# board.net
KiCad netlist of a schematic drawn in EAGLE
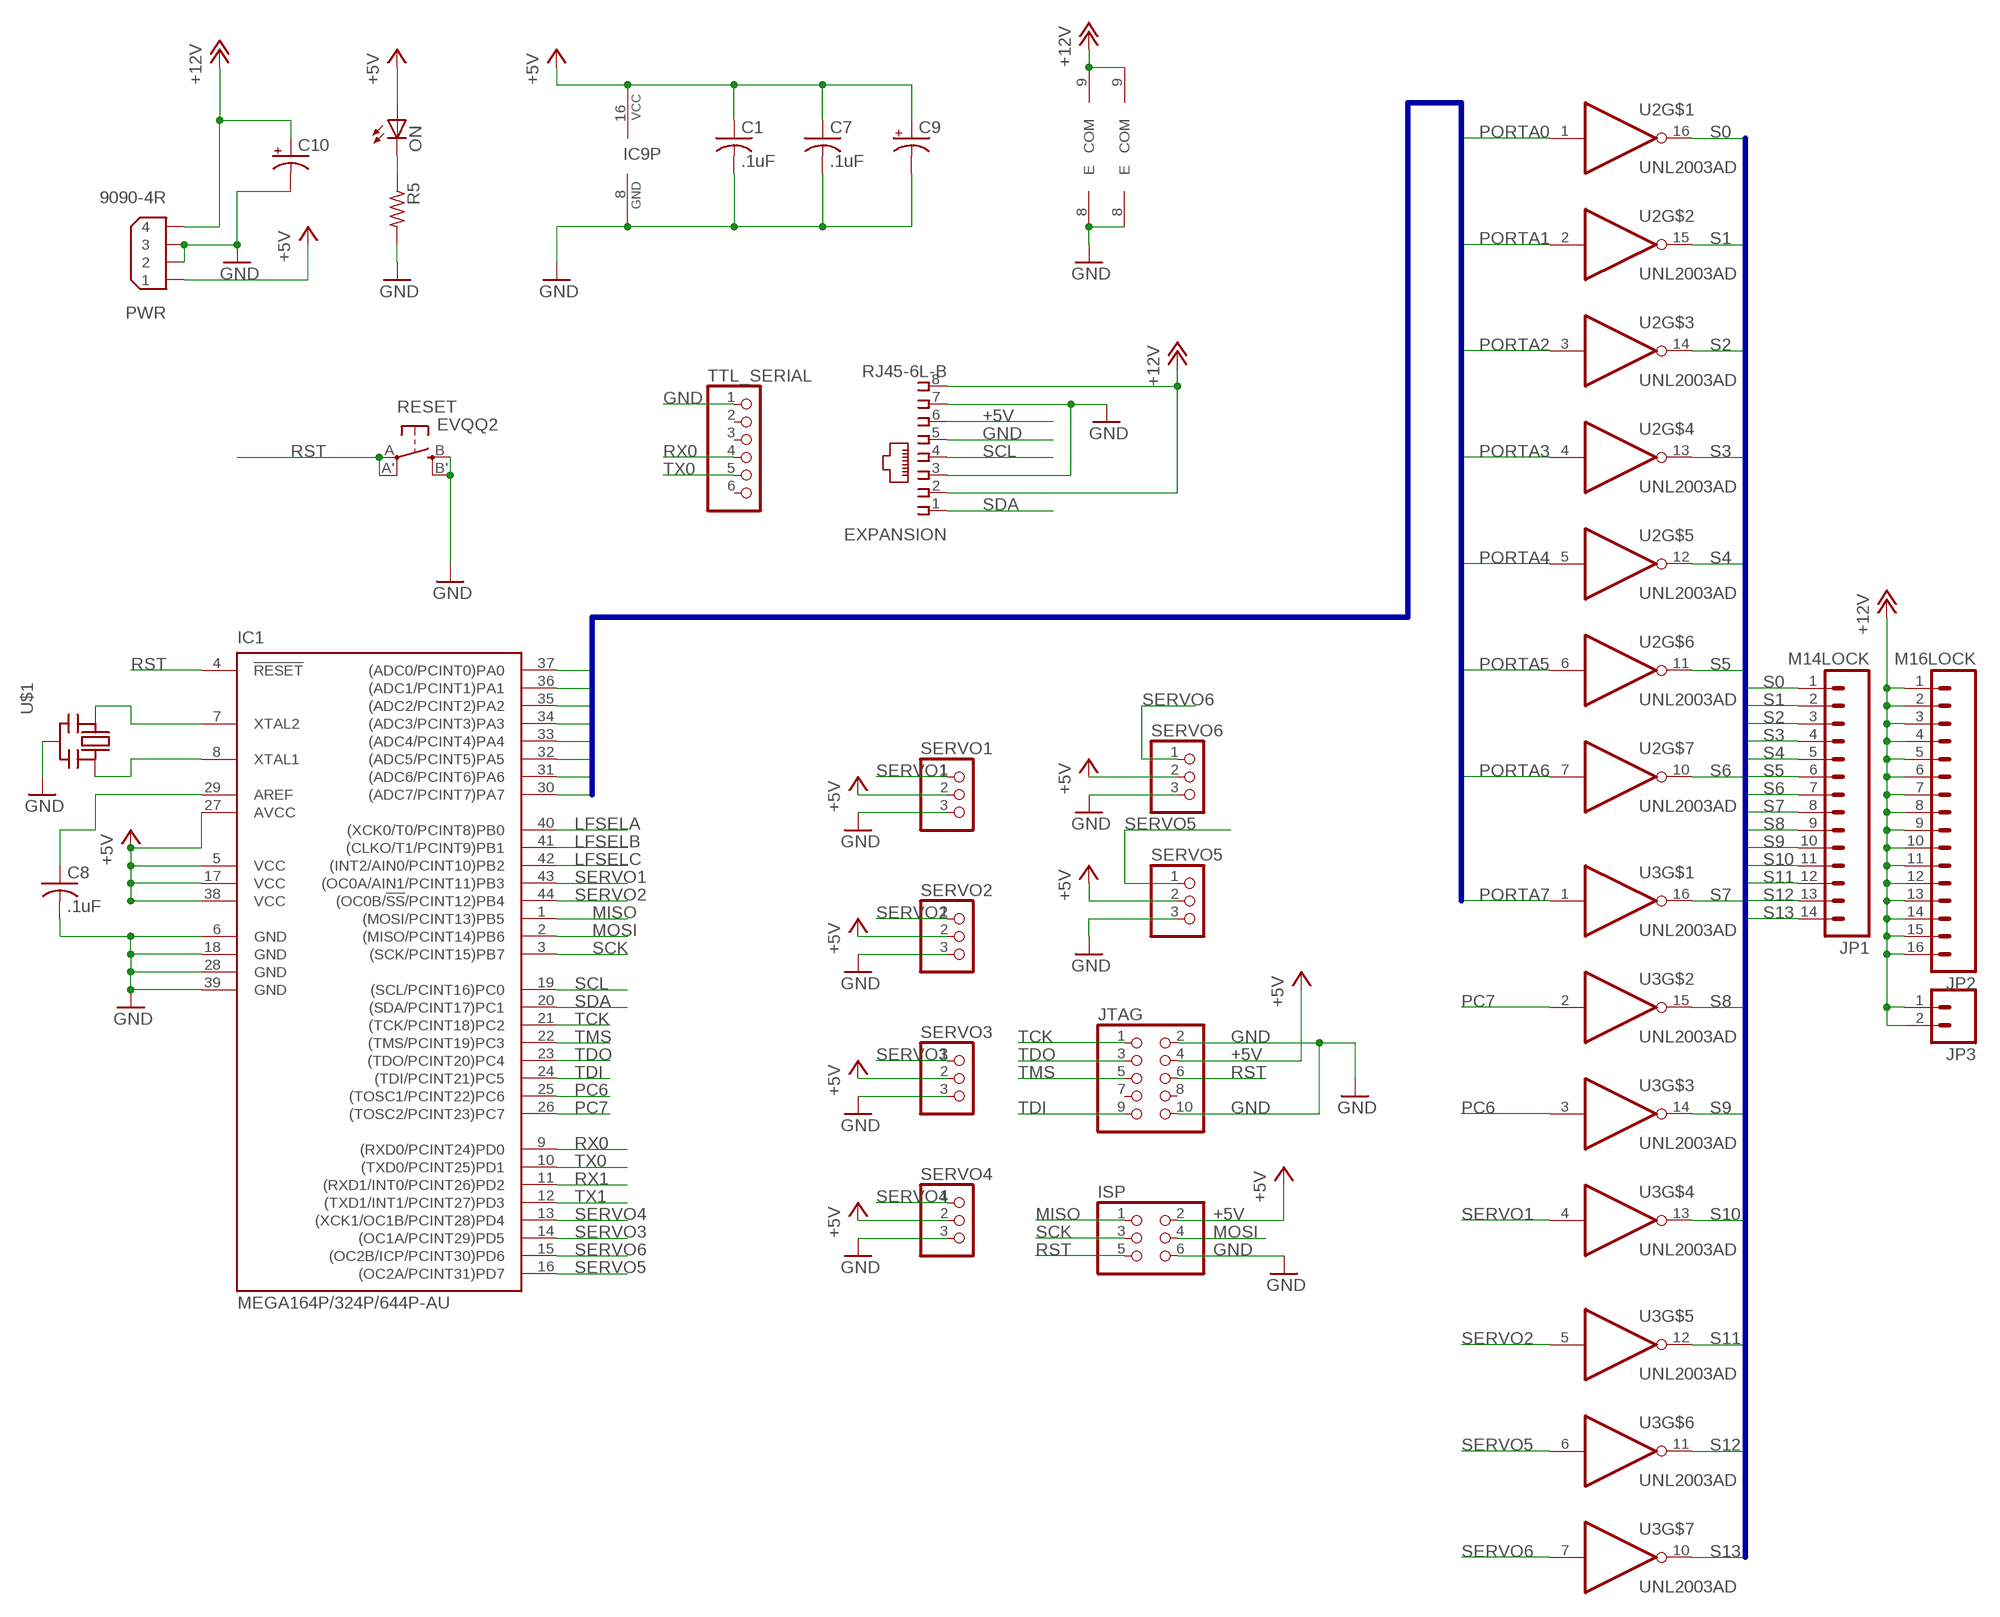
[diagram p0: schematic, sheet 1, part 1 of 2]
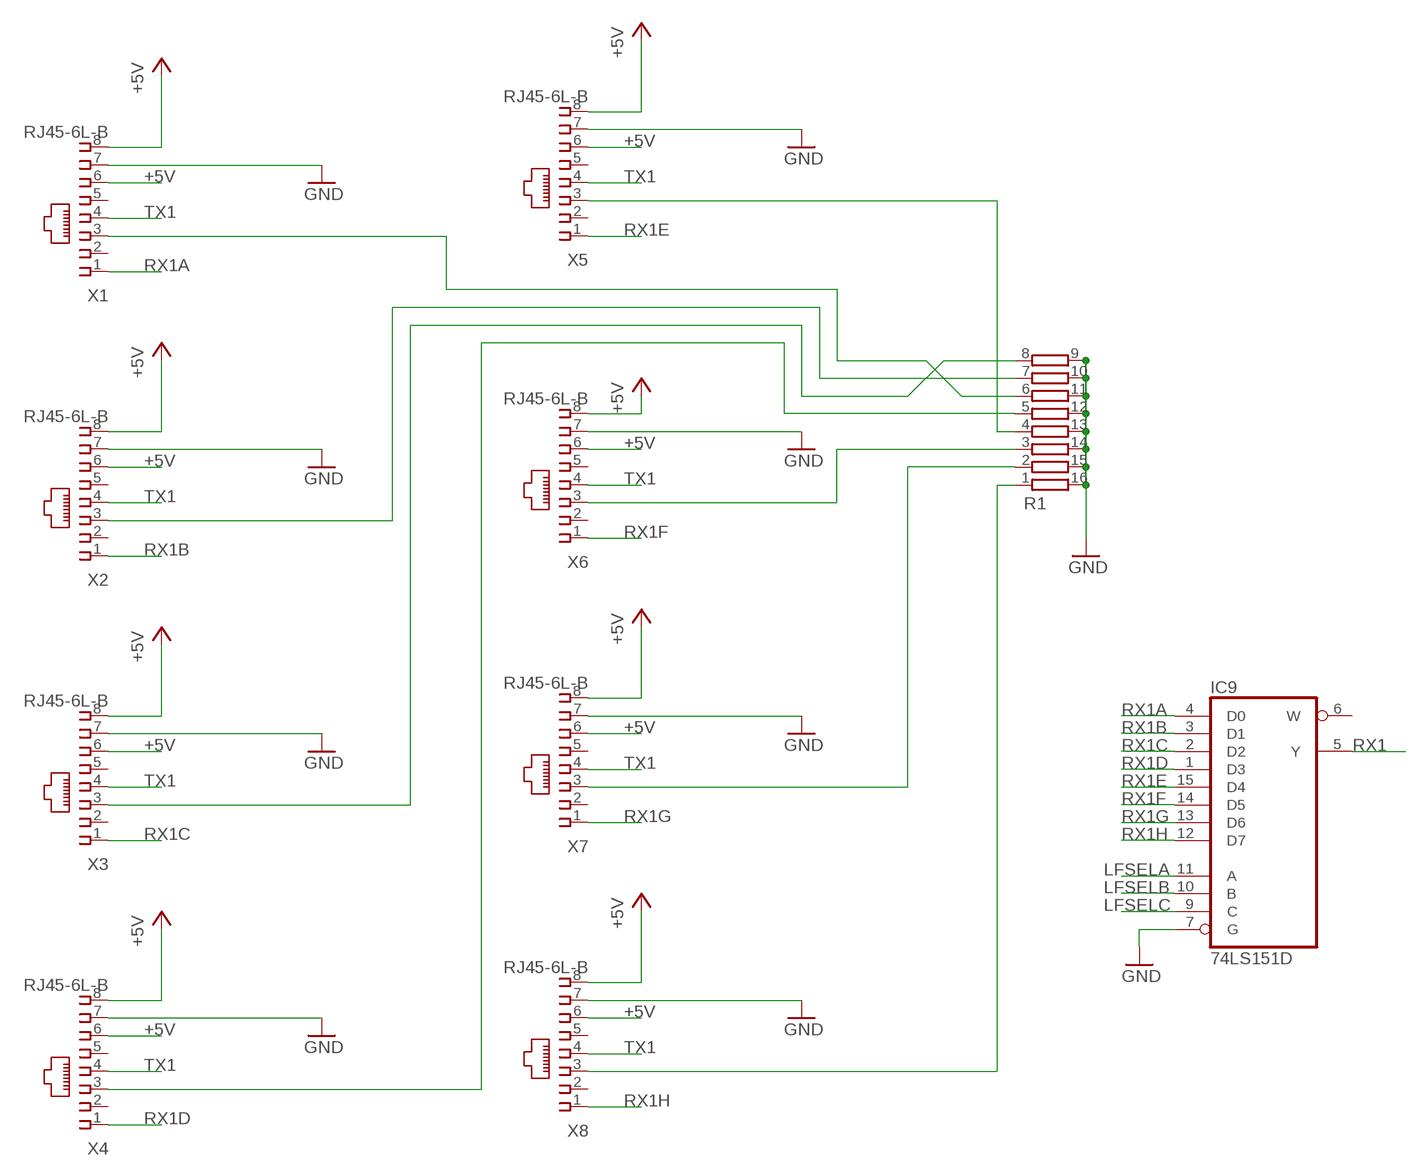
[diagram p1: schematic, sheet 1, part 2 of 2]

(export (version "E")
  (design (tool "Eeschema 10.0.6"))
  (components
    (comp (ref "C1")
      (value ".1uF")
      (footprint "eagle-import:C0805")
      (libsource (lib "eagle-import") (part "C-USC0805"))
    )
    (comp (ref "C7")
      (value ".1uF")
      (footprint "eagle-import:C0805")
      (libsource (lib "eagle-import") (part "C-USC0805"))
    )
    (comp (ref "C8")
      (value ".1uF")
      (footprint "eagle-import:C0805")
      (libsource (lib "eagle-import") (part "C-USC0805"))
    )
    (comp (ref "C9")
      (value "CPOL-USE2.5-7")
      (footprint "eagle-import:E2,5-7")
      (libsource (lib "eagle-import") (part "CPOL-USE2.5-7"))
    )
    (comp (ref "C10")
      (value "CPOL-USE2.5-7")
      (footprint "eagle-import:E2,5-7")
      (libsource (lib "eagle-import") (part "CPOL-USE2.5-7"))
    )
    (comp (ref "EXPANSION")
      (value "RJ45-6L-B")
      (footprint "eagle-import:RJ45-NO-SHIELD")
      (libsource (lib "eagle-import") (part "RJ45-6L-B"))
    )
    (comp (ref "IC1")
      (value "MEGA164P/324P/644P-AU")
      (footprint "eagle-import:TQFP44")
      (libsource (lib "eagle-import") (part "MEGA164P/324P/644P-AU"))
    )
    (comp (ref "IC9")
      (value "74LS151D")
      (footprint "eagle-import:SO16")
      (libsource (lib "eagle-import") (part "74151DLS"))
    )
    (comp (ref "ISP")
      (value "PINHD-2X3")
      (footprint "eagle-import:2X03")
      (libsource (lib "eagle-import") (part "PINHD-2X3"))
    )
    (comp (ref "JP1")
      (value "M14LOCK")
      (footprint "eagle-import:1X14_LOCK")
      (libsource (lib "eagle-import") (part "M14LOCK"))
    )
    (comp (ref "JP2")
      (value "M16LOCK")
      (footprint "eagle-import:1X16_LOCK")
      (libsource (lib "eagle-import") (part "M16LOCK"))
    )
    (comp (ref "JP3")
      (value "M02PTH")
      (footprint "eagle-import:1X02")
      (libsource (lib "eagle-import") (part "M02PTH"))
    )
    (comp (ref "JTAG")
      (value "PINHD-2X5")
      (footprint "eagle-import:2X05")
      (libsource (lib "eagle-import") (part "PINHD-2X5"))
    )
    (comp (ref "ON")
      (value "LEDCHIPLED_0805")
      (footprint "eagle-import:CHIPLED_0805")
      (libsource (lib "eagle-import") (part "LEDCHIPLED_0805"))
    )
    (comp (ref "PWR")
      (value "9090-4R")
      (footprint "eagle-import:9090-4R")
      (libsource (lib "eagle-import") (part "9090-4R"))
    )
    (comp (ref "R1")
      (value "2NBS16-8")
      (footprint "eagle-import:SO16")
      (libsource (lib "eagle-import") (part "2NBS16-8"))
    )
    (comp (ref "R5")
      (value "R-US_R0805")
      (footprint "eagle-import:R0805")
      (libsource (lib "eagle-import") (part "R-US_R0805"))
    )
    (comp (ref "RESET")
      (value "EVQQ2")
      (footprint "eagle-import:EVQ-Q2")
      (libsource (lib "eagle-import") (part "EVQQ2"))
    )
    (comp (ref "SERVO1")
      (value "PINHD-1X3")
      (footprint "eagle-import:1X03")
      (libsource (lib "eagle-import") (part "PINHD-1X3"))
    )
    (comp (ref "SERVO2")
      (value "PINHD-1X3")
      (footprint "eagle-import:1X03")
      (libsource (lib "eagle-import") (part "PINHD-1X3"))
    )
    (comp (ref "SERVO3")
      (value "PINHD-1X3")
      (footprint "eagle-import:1X03")
      (libsource (lib "eagle-import") (part "PINHD-1X3"))
    )
    (comp (ref "SERVO4")
      (value "PINHD-1X3")
      (footprint "eagle-import:1X03")
      (libsource (lib "eagle-import") (part "PINHD-1X3"))
    )
    (comp (ref "SERVO5")
      (value "PINHD-1X3")
      (footprint "eagle-import:1X03")
      (libsource (lib "eagle-import") (part "PINHD-1X3"))
    )
    (comp (ref "SERVO6")
      (value "PINHD-1X3")
      (footprint "eagle-import:1X03")
      (libsource (lib "eagle-import") (part "PINHD-1X3"))
    )
    (comp (ref "TTL_SERIAL")
      (value "PINHD-1X6")
      (footprint "eagle-import:1X06")
      (libsource (lib "eagle-import") (part "PINHD-1X6"))
    )
    (comp (ref "U$1")
      (value "CERMOSCILL-CSTCRG")
      (footprint "eagle-import:CSTCR-G")
      (libsource (lib "eagle-import") (part "CERMOSCILL-CSTCRG"))
    )
    (comp (ref "U2")
      (value "UNL2003AD")
      (footprint "eagle-import:SO16")
      (libsource (lib "eagle-import") (part "UNL2003AD"))
    )
    (comp (ref "U3")
      (value "UNL2003AD")
      (footprint "eagle-import:SO16")
      (libsource (lib "eagle-import") (part "UNL2003AD"))
    )
    (comp (ref "X1")
      (value "RJ45-6L-B")
      (footprint "eagle-import:RJ45-NO-SHIELD")
      (libsource (lib "eagle-import") (part "RJ45-6L-B"))
    )
    (comp (ref "X2")
      (value "RJ45-6L-B")
      (footprint "eagle-import:RJ45-NO-SHIELD")
      (libsource (lib "eagle-import") (part "RJ45-6L-B"))
    )
    (comp (ref "X3")
      (value "RJ45-6L-B")
      (footprint "eagle-import:RJ45-NO-SHIELD")
      (libsource (lib "eagle-import") (part "RJ45-6L-B"))
    )
    (comp (ref "X4")
      (value "RJ45-6L-B")
      (footprint "eagle-import:RJ45-NO-SHIELD")
      (libsource (lib "eagle-import") (part "RJ45-6L-B"))
    )
    (comp (ref "X5")
      (value "RJ45-6L-B")
      (footprint "eagle-import:RJ45-NO-SHIELD")
      (libsource (lib "eagle-import") (part "RJ45-6L-B"))
    )
    (comp (ref "X6")
      (value "RJ45-6L-B")
      (footprint "eagle-import:RJ45-NO-SHIELD")
      (libsource (lib "eagle-import") (part "RJ45-6L-B"))
    )
    (comp (ref "X7")
      (value "RJ45-6L-B")
      (footprint "eagle-import:RJ45-NO-SHIELD")
      (libsource (lib "eagle-import") (part "RJ45-6L-B"))
    )
    (comp (ref "X8")
      (value "RJ45-6L-B")
      (footprint "eagle-import:RJ45-NO-SHIELD")
      (libsource (lib "eagle-import") (part "RJ45-6L-B"))
    )
  )
  (nets
    (net (code "1") (name "+5V") (class "Default")
      (node (ref "C1") (pin "1") (pinfunction "1_1") (pintype "passive"))
      (node (ref "C7") (pin "1") (pinfunction "1_1") (pintype "passive"))
      (node (ref "C9") (pin "+") (pinfunction "+_+") (pintype "passive"))
      (node (ref "EXPANSION") (pin "6") (pinfunction "6_6") (pintype "passive"))
      (node (ref "IC1") (pin "17") (pinfunction "VCC_17") (pintype "power_in"))
      (node (ref "IC1") (pin "27") (pinfunction "AVCC_27") (pintype "power_in"))
      (node (ref "IC1") (pin "38") (pinfunction "VCC_38") (pintype "power_in"))
      (node (ref "IC1") (pin "5") (pinfunction "VCC_5") (pintype "power_in"))
      (node (ref "IC9") (pin "16") (pinfunction "VCC_16") (pintype "power_in"))
      (node (ref "ISP") (pin "2") (pinfunction "2_2") (pintype "passive"))
      (node (ref "JTAG") (pin "4") (pinfunction "4_4") (pintype "passive"))
      (node (ref "ON") (pin "A") (pinfunction "A_A") (pintype "passive"))
      (node (ref "PWR") (pin "1") (pinfunction "1_1") (pintype "passive"))
      (node (ref "SERVO1") (pin "2") (pinfunction "2_2") (pintype "passive"))
      (node (ref "SERVO2") (pin "2") (pinfunction "2_2") (pintype "passive"))
      (node (ref "SERVO3") (pin "2") (pinfunction "2_2") (pintype "passive"))
      (node (ref "SERVO4") (pin "2") (pinfunction "2_2") (pintype "passive"))
      (node (ref "SERVO5") (pin "2") (pinfunction "2_2") (pintype "passive"))
      (node (ref "SERVO6") (pin "2") (pinfunction "2_2") (pintype "passive"))
      (node (ref "X1") (pin "6") (pinfunction "6_6") (pintype "passive"))
      (node (ref "X1") (pin "8") (pinfunction "8_8") (pintype "passive"))
      (node (ref "X2") (pin "6") (pinfunction "6_6") (pintype "passive"))
      (node (ref "X2") (pin "8") (pinfunction "8_8") (pintype "passive"))
      (node (ref "X3") (pin "6") (pinfunction "6_6") (pintype "passive"))
      (node (ref "X3") (pin "8") (pinfunction "8_8") (pintype "passive"))
      (node (ref "X4") (pin "6") (pinfunction "6_6") (pintype "passive"))
      (node (ref "X4") (pin "8") (pinfunction "8_8") (pintype "passive"))
      (node (ref "X5") (pin "6") (pinfunction "6_6") (pintype "passive"))
      (node (ref "X5") (pin "8") (pinfunction "8_8") (pintype "passive"))
      (node (ref "X6") (pin "6") (pinfunction "6_6") (pintype "passive"))
      (node (ref "X6") (pin "8") (pinfunction "8_8") (pintype "passive"))
      (node (ref "X7") (pin "6") (pinfunction "6_6") (pintype "passive"))
      (node (ref "X7") (pin "8") (pinfunction "8_8") (pintype "passive"))
      (node (ref "X8") (pin "6") (pinfunction "6_6") (pintype "passive"))
      (node (ref "X8") (pin "8") (pinfunction "8_8") (pintype "passive"))
    )
    (net (code "2") (name "+12V") (class "Default")
      (node (ref "C10") (pin "+") (pinfunction "+_+") (pintype "passive"))
      (node (ref "EXPANSION") (pin "2") (pinfunction "2_2") (pintype "passive"))
      (node (ref "EXPANSION") (pin "8") (pinfunction "8_8") (pintype "passive"))
      (node (ref "JP2") (pin "1") (pinfunction "1_1") (pintype "passive"))
      (node (ref "JP2") (pin "10") (pinfunction "10_10") (pintype "passive"))
      (node (ref "JP2") (pin "11") (pinfunction "11_11") (pintype "passive"))
      (node (ref "JP2") (pin "12") (pinfunction "12_12") (pintype "passive"))
      (node (ref "JP2") (pin "13") (pinfunction "13_13") (pintype "passive"))
      (node (ref "JP2") (pin "14") (pinfunction "14_14") (pintype "passive"))
      (node (ref "JP2") (pin "15") (pinfunction "15_15") (pintype "passive"))
      (node (ref "JP2") (pin "16") (pinfunction "16_16") (pintype "passive"))
      (node (ref "JP2") (pin "2") (pinfunction "2_2") (pintype "passive"))
      (node (ref "JP2") (pin "3") (pinfunction "3_3") (pintype "passive"))
      (node (ref "JP2") (pin "4") (pinfunction "4_4") (pintype "passive"))
      (node (ref "JP2") (pin "5") (pinfunction "5_5") (pintype "passive"))
      (node (ref "JP2") (pin "6") (pinfunction "6_6") (pintype "passive"))
      (node (ref "JP2") (pin "7") (pinfunction "7_7") (pintype "passive"))
      (node (ref "JP2") (pin "8") (pinfunction "8_8") (pintype "passive"))
      (node (ref "JP2") (pin "9") (pinfunction "9_9") (pintype "passive"))
      (node (ref "JP3") (pin "1") (pinfunction "1_1") (pintype "passive"))
      (node (ref "JP3") (pin "2") (pinfunction "2_2") (pintype "passive"))
      (node (ref "PWR") (pin "4") (pinfunction "4_4") (pintype "passive"))
      (node (ref "U2") (pin "9") (pinfunction "COM_9") (pintype "power_in"))
      (node (ref "U3") (pin "9") (pinfunction "COM_9") (pintype "power_in"))
    )
    (net (code "3") (name "/LFSELA") (class "Default")
      (node (ref "IC1") (pin "40") (pinfunction "(XCK0/T0/PCINT8)PB0_40") (pintype "bidirectional"))
      (node (ref "IC9") (pin "11") (pinfunction "A_11") (pintype "input"))
    )
    (net (code "4") (name "/LFSELB") (class "Default")
      (node (ref "IC1") (pin "41") (pinfunction "(CLKO/T1/PCINT9)PB1_41") (pintype "bidirectional"))
      (node (ref "IC9") (pin "10") (pinfunction "B_10") (pintype "input"))
    )
    (net (code "5") (name "/LFSELC") (class "Default")
      (node (ref "IC1") (pin "42") (pinfunction "(INT2/AIN0/PCINT10)PB2_42") (pintype "bidirectional"))
      (node (ref "IC9") (pin "9") (pinfunction "C_9") (pintype "input"))
    )
    (net (code "6") (name "/MISO") (class "Default")
      (node (ref "IC1") (pin "1") (pinfunction "(MOSI/PCINT13)PB5_1") (pintype "bidirectional"))
      (node (ref "ISP") (pin "1") (pinfunction "1_1") (pintype "passive"))
    )
    (net (code "7") (name "/MOSI") (class "Default")
      (node (ref "IC1") (pin "2") (pinfunction "(MISO/PCINT14)PB6_2") (pintype "bidirectional"))
      (node (ref "ISP") (pin "4") (pinfunction "4_4") (pintype "passive"))
    )
    (net (code "8") (name "/PC6") (class "Default")
      (node (ref "IC1") (pin "25") (pinfunction "(TOSC1/PCINT22)PC6_25") (pintype "bidirectional"))
      (node (ref "U3") (pin "3") (pinfunction "I_3") (pintype "input"))
    )
    (net (code "9") (name "/PC7") (class "Default")
      (node (ref "IC1") (pin "26") (pinfunction "(TOSC2/PCINT23)PC7_26") (pintype "bidirectional"))
      (node (ref "U3") (pin "2") (pinfunction "I_2") (pintype "input"))
    )
    (net (code "10") (name "/PORTA0") (class "Default")
      (node (ref "IC1") (pin "37") (pinfunction "(ADC0/PCINT0)PA0_37") (pintype "bidirectional"))
      (node (ref "U2") (pin "1") (pinfunction "I_1") (pintype "input"))
    )
    (net (code "11") (name "/PORTA1") (class "Default")
      (node (ref "IC1") (pin "36") (pinfunction "(ADC1/PCINT1)PA1_36") (pintype "bidirectional"))
      (node (ref "U2") (pin "2") (pinfunction "I_2") (pintype "input"))
    )
    (net (code "12") (name "/PORTA2") (class "Default")
      (node (ref "IC1") (pin "35") (pinfunction "(ADC2/PCINT2)PA2_35") (pintype "bidirectional"))
      (node (ref "U2") (pin "3") (pinfunction "I_3") (pintype "input"))
    )
    (net (code "13") (name "/PORTA3") (class "Default")
      (node (ref "IC1") (pin "34") (pinfunction "(ADC3/PCINT3)PA3_34") (pintype "bidirectional"))
      (node (ref "U2") (pin "4") (pinfunction "I_4") (pintype "input"))
    )
    (net (code "14") (name "/PORTA4") (class "Default")
      (node (ref "IC1") (pin "33") (pinfunction "(ADC4/PCINT4)PA4_33") (pintype "bidirectional"))
      (node (ref "U2") (pin "5") (pinfunction "I_5") (pintype "input"))
    )
    (net (code "15") (name "/PORTA5") (class "Default")
      (node (ref "IC1") (pin "32") (pinfunction "(ADC5/PCINT5)PA5_32") (pintype "bidirectional"))
      (node (ref "U2") (pin "6") (pinfunction "I_6") (pintype "input"))
    )
    (net (code "16") (name "/PORTA6") (class "Default")
      (node (ref "IC1") (pin "31") (pinfunction "(ADC6/PCINT6)PA6_31") (pintype "bidirectional"))
      (node (ref "U2") (pin "7") (pinfunction "I_7") (pintype "input"))
    )
    (net (code "17") (name "/PORTA7") (class "Default")
      (node (ref "IC1") (pin "30") (pinfunction "(ADC7/PCINT7)PA7_30") (pintype "bidirectional"))
      (node (ref "U3") (pin "1") (pinfunction "I_1") (pintype "input"))
    )
    (net (code "18") (name "/RST") (class "Default")
      (node (ref "IC1") (pin "4") (pinfunction "~{RESET}_4") (pintype "input"))
      (node (ref "ISP") (pin "5") (pinfunction "5_5") (pintype "passive"))
      (node (ref "JTAG") (pin "6") (pinfunction "6_6") (pintype "passive"))
      (node (ref "RESET") (pin "A") (pinfunction "P_A") (pintype "passive"))
      (node (ref "RESET") (pin "A'") (pinfunction "P1_A'") (pintype "passive"))
    )
    (net (code "19") (name "/RX0") (class "Default")
      (node (ref "IC1") (pin "9") (pinfunction "(RXD0/PCINT24)PD0_9") (pintype "bidirectional"))
      (node (ref "TTL_SERIAL") (pin "4") (pinfunction "4_4") (pintype "passive"))
    )
    (net (code "20") (name "/RX1") (class "Default")
      (node (ref "IC1") (pin "11") (pinfunction "(RXD1/INT0/PCINT26)PD2_11") (pintype "bidirectional"))
      (node (ref "IC9") (pin "5") (pinfunction "Y_5") (pintype "output"))
    )
    (net (code "21") (name "/RX1A") (class "Default")
      (node (ref "IC9") (pin "4") (pinfunction "D0_4") (pintype "input"))
      (node (ref "X1") (pin "1") (pinfunction "1_1") (pintype "passive"))
    )
    (net (code "22") (name "/RX1B") (class "Default")
      (node (ref "IC9") (pin "3") (pinfunction "D1_3") (pintype "input"))
      (node (ref "X2") (pin "1") (pinfunction "1_1") (pintype "passive"))
    )
    (net (code "23") (name "/RX1C") (class "Default")
      (node (ref "IC9") (pin "2") (pinfunction "D2_2") (pintype "input"))
      (node (ref "X3") (pin "1") (pinfunction "1_1") (pintype "passive"))
    )
    (net (code "24") (name "/RX1D") (class "Default")
      (node (ref "IC9") (pin "1") (pinfunction "D3_1") (pintype "input"))
      (node (ref "X4") (pin "1") (pinfunction "1_1") (pintype "passive"))
    )
    (net (code "25") (name "/RX1E") (class "Default")
      (node (ref "IC9") (pin "15") (pinfunction "D4_15") (pintype "input"))
      (node (ref "X5") (pin "1") (pinfunction "1_1") (pintype "passive"))
    )
    (net (code "26") (name "/RX1F") (class "Default")
      (node (ref "IC9") (pin "14") (pinfunction "D5_14") (pintype "input"))
      (node (ref "X6") (pin "1") (pinfunction "1_1") (pintype "passive"))
    )
    (net (code "27") (name "/RX1G") (class "Default")
      (node (ref "IC9") (pin "13") (pinfunction "D6_13") (pintype "input"))
      (node (ref "X7") (pin "1") (pinfunction "1_1") (pintype "passive"))
    )
    (net (code "28") (name "/RX1H") (class "Default")
      (node (ref "IC9") (pin "12") (pinfunction "D7_12") (pintype "input"))
      (node (ref "X8") (pin "1") (pinfunction "1_1") (pintype "passive"))
    )
    (net (code "29") (name "/S0") (class "Default")
      (node (ref "JP1") (pin "1") (pinfunction "1_1") (pintype "passive"))
      (node (ref "U2") (pin "16") (pinfunction "O_16") (pintype "output"))
    )
    (net (code "30") (name "/S1") (class "Default")
      (node (ref "JP1") (pin "2") (pinfunction "2_2") (pintype "passive"))
      (node (ref "U2") (pin "15") (pinfunction "O_15") (pintype "output"))
    )
    (net (code "31") (name "/S2") (class "Default")
      (node (ref "JP1") (pin "3") (pinfunction "3_3") (pintype "passive"))
      (node (ref "U2") (pin "14") (pinfunction "O_14") (pintype "output"))
    )
    (net (code "32") (name "/S3") (class "Default")
      (node (ref "JP1") (pin "4") (pinfunction "4_4") (pintype "passive"))
      (node (ref "U2") (pin "13") (pinfunction "O_13") (pintype "output"))
    )
    (net (code "33") (name "/S4") (class "Default")
      (node (ref "JP1") (pin "5") (pinfunction "5_5") (pintype "passive"))
      (node (ref "U2") (pin "12") (pinfunction "O_12") (pintype "output"))
    )
    (net (code "34") (name "/S5") (class "Default")
      (node (ref "JP1") (pin "6") (pinfunction "6_6") (pintype "passive"))
      (node (ref "U2") (pin "11") (pinfunction "O_11") (pintype "output"))
    )
    (net (code "35") (name "/S6") (class "Default")
      (node (ref "JP1") (pin "7") (pinfunction "7_7") (pintype "passive"))
      (node (ref "U2") (pin "10") (pinfunction "O_10") (pintype "output"))
    )
    (net (code "36") (name "/S7") (class "Default")
      (node (ref "JP1") (pin "8") (pinfunction "8_8") (pintype "passive"))
      (node (ref "U3") (pin "16") (pinfunction "O_16") (pintype "output"))
    )
    (net (code "37") (name "/S8") (class "Default")
      (node (ref "JP1") (pin "9") (pinfunction "9_9") (pintype "passive"))
      (node (ref "U3") (pin "15") (pinfunction "O_15") (pintype "output"))
    )
    (net (code "38") (name "/S9") (class "Default")
      (node (ref "JP1") (pin "10") (pinfunction "10_10") (pintype "passive"))
      (node (ref "U3") (pin "14") (pinfunction "O_14") (pintype "output"))
    )
    (net (code "39") (name "/S10") (class "Default")
      (node (ref "JP1") (pin "11") (pinfunction "11_11") (pintype "passive"))
      (node (ref "U3") (pin "13") (pinfunction "O_13") (pintype "output"))
    )
    (net (code "40") (name "/S11") (class "Default")
      (node (ref "JP1") (pin "12") (pinfunction "12_12") (pintype "passive"))
      (node (ref "U3") (pin "12") (pinfunction "O_12") (pintype "output"))
    )
    (net (code "41") (name "/S12") (class "Default")
      (node (ref "JP1") (pin "13") (pinfunction "13_13") (pintype "passive"))
      (node (ref "U3") (pin "11") (pinfunction "O_11") (pintype "output"))
    )
    (net (code "42") (name "/S13") (class "Default")
      (node (ref "JP1") (pin "14") (pinfunction "14_14") (pintype "passive"))
      (node (ref "U3") (pin "10") (pinfunction "O_10") (pintype "output"))
    )
    (net (code "43") (name "/SCK") (class "Default")
      (node (ref "IC1") (pin "3") (pinfunction "(SCK/PCINT15)PB7_3") (pintype "bidirectional"))
      (node (ref "ISP") (pin "3") (pinfunction "3_3") (pintype "passive"))
    )
    (net (code "44") (name "/SCL") (class "Default")
      (node (ref "EXPANSION") (pin "4") (pinfunction "4_4") (pintype "passive"))
      (node (ref "IC1") (pin "19") (pinfunction "(SCL/PCINT16)PC0_19") (pintype "bidirectional"))
    )
    (net (code "45") (name "/SDA") (class "Default")
      (node (ref "EXPANSION") (pin "1") (pinfunction "1_1") (pintype "passive"))
      (node (ref "IC1") (pin "20") (pinfunction "(SDA/PCINT17)PC1_20") (pintype "bidirectional"))
    )
    (net (code "46") (name "/SERVO1") (class "Default")
      (node (ref "IC1") (pin "43") (pinfunction "(OC0A/AIN1/PCINT11)PB3_43") (pintype "bidirectional"))
      (node (ref "SERVO1") (pin "1") (pinfunction "1_1") (pintype "passive"))
      (node (ref "U3") (pin "4") (pinfunction "I_4") (pintype "input"))
    )
    (net (code "47") (name "/SERVO2") (class "Default")
      (node (ref "IC1") (pin "44") (pinfunction "(OC0B/~{SS}/PCINT12)PB4_44") (pintype "bidirectional"))
      (node (ref "SERVO2") (pin "1") (pinfunction "1_1") (pintype "passive"))
      (node (ref "U3") (pin "5") (pinfunction "I_5") (pintype "input"))
    )
    (net (code "48") (name "/SERVO3") (class "Default")
      (node (ref "IC1") (pin "14") (pinfunction "(OC1A/PCINT29)PD5_14") (pintype "bidirectional"))
      (node (ref "SERVO3") (pin "1") (pinfunction "1_1") (pintype "passive"))
    )
    (net (code "49") (name "/SERVO4") (class "Default")
      (node (ref "IC1") (pin "13") (pinfunction "(XCK1/OC1B/PCINT28)PD4_13") (pintype "bidirectional"))
      (node (ref "SERVO4") (pin "1") (pinfunction "1_1") (pintype "passive"))
    )
    (net (code "50") (name "/SERVO5") (class "Default")
      (node (ref "IC1") (pin "16") (pinfunction "(OC2A/PCINT31)PD7_16") (pintype "bidirectional"))
      (node (ref "SERVO5") (pin "1") (pinfunction "1_1") (pintype "passive"))
      (node (ref "U3") (pin "6") (pinfunction "I_6") (pintype "input"))
    )
    (net (code "51") (name "/SERVO6") (class "Default")
      (node (ref "IC1") (pin "15") (pinfunction "(OC2B/ICP/PCINT30)PD6_15") (pintype "bidirectional"))
      (node (ref "SERVO6") (pin "1") (pinfunction "1_1") (pintype "passive"))
      (node (ref "U3") (pin "7") (pinfunction "I_7") (pintype "input"))
    )
    (net (code "52") (name "/TCK") (class "Default")
      (node (ref "IC1") (pin "21") (pinfunction "(TCK/PCINT18)PC2_21") (pintype "bidirectional"))
      (node (ref "JTAG") (pin "1") (pinfunction "1_1") (pintype "passive"))
    )
    (net (code "53") (name "/TDI") (class "Default")
      (node (ref "IC1") (pin "24") (pinfunction "(TDI/PCINT21)PC5_24") (pintype "bidirectional"))
      (node (ref "JTAG") (pin "9") (pinfunction "9_9") (pintype "passive"))
    )
    (net (code "54") (name "/TDO") (class "Default")
      (node (ref "IC1") (pin "23") (pinfunction "(TDO/PCINT20)PC4_23") (pintype "bidirectional"))
      (node (ref "JTAG") (pin "3") (pinfunction "3_3") (pintype "passive"))
    )
    (net (code "55") (name "/TMS") (class "Default")
      (node (ref "IC1") (pin "22") (pinfunction "(TMS/PCINT19)PC3_22") (pintype "bidirectional"))
      (node (ref "JTAG") (pin "5") (pinfunction "5_5") (pintype "passive"))
    )
    (net (code "56") (name "/TX0") (class "Default")
      (node (ref "IC1") (pin "10") (pinfunction "(TXD0/PCINT25)PD1_10") (pintype "bidirectional"))
      (node (ref "TTL_SERIAL") (pin "5") (pinfunction "5_5") (pintype "passive"))
    )
    (net (code "57") (name "/TX1") (class "Default")
      (node (ref "IC1") (pin "12") (pinfunction "(TXD1/INT1/PCINT27)PD3_12") (pintype "bidirectional"))
      (node (ref "X1") (pin "4") (pinfunction "4_4") (pintype "passive"))
      (node (ref "X2") (pin "4") (pinfunction "4_4") (pintype "passive"))
      (node (ref "X3") (pin "4") (pinfunction "4_4") (pintype "passive"))
      (node (ref "X4") (pin "4") (pinfunction "4_4") (pintype "passive"))
      (node (ref "X5") (pin "4") (pinfunction "4_4") (pintype "passive"))
      (node (ref "X6") (pin "4") (pinfunction "4_4") (pintype "passive"))
      (node (ref "X7") (pin "4") (pinfunction "4_4") (pintype "passive"))
      (node (ref "X8") (pin "4") (pinfunction "4_4") (pintype "passive"))
    )
    (net (code "58") (name "GND") (class "Default")
      (node (ref "C1") (pin "2") (pinfunction "2_2") (pintype "passive"))
      (node (ref "C10") (pin "-") (pinfunction "-_-") (pintype "passive"))
      (node (ref "C7") (pin "2") (pinfunction "2_2") (pintype "passive"))
      (node (ref "C8") (pin "2") (pinfunction "2_2") (pintype "passive"))
      (node (ref "C9") (pin "-") (pinfunction "-_-") (pintype "passive"))
      (node (ref "EXPANSION") (pin "3") (pinfunction "3_3") (pintype "passive"))
      (node (ref "EXPANSION") (pin "5") (pinfunction "5_5") (pintype "passive"))
      (node (ref "EXPANSION") (pin "7") (pinfunction "7_7") (pintype "passive"))
      (node (ref "IC1") (pin "18") (pinfunction "GND_18") (pintype "power_in"))
      (node (ref "IC1") (pin "28") (pinfunction "GND_28") (pintype "power_in"))
      (node (ref "IC1") (pin "39") (pinfunction "GND_39") (pintype "power_in"))
      (node (ref "IC1") (pin "6") (pinfunction "GND_6") (pintype "power_in"))
      (node (ref "IC9") (pin "7") (pinfunction "G_7") (pintype "input"))
      (node (ref "IC9") (pin "8") (pinfunction "GND_8") (pintype "power_in"))
      (node (ref "ISP") (pin "6") (pinfunction "6_6") (pintype "passive"))
      (node (ref "JTAG") (pin "10") (pinfunction "10_10") (pintype "passive"))
      (node (ref "JTAG") (pin "2") (pinfunction "2_2") (pintype "passive"))
      (node (ref "PWR") (pin "2") (pinfunction "2_2") (pintype "passive"))
      (node (ref "PWR") (pin "3") (pinfunction "3_3") (pintype "passive"))
      (node (ref "R1") (pin "10") (pinfunction "10_10") (pintype "passive"))
      (node (ref "R1") (pin "11") (pinfunction "11_11") (pintype "passive"))
      (node (ref "R1") (pin "12") (pinfunction "12_12") (pintype "passive"))
      (node (ref "R1") (pin "13") (pinfunction "13_13") (pintype "passive"))
      (node (ref "R1") (pin "14") (pinfunction "14_14") (pintype "passive"))
      (node (ref "R1") (pin "15") (pinfunction "15_15") (pintype "passive"))
      (node (ref "R1") (pin "16") (pinfunction "16_16") (pintype "passive"))
      (node (ref "R1") (pin "9") (pinfunction "9_9") (pintype "passive"))
      (node (ref "R5") (pin "2") (pinfunction "2_2") (pintype "passive"))
      (node (ref "RESET") (pin "B") (pinfunction "S_B") (pintype "passive"))
      (node (ref "RESET") (pin "B'") (pinfunction "S1_B'") (pintype "passive"))
      (node (ref "SERVO1") (pin "3") (pinfunction "3_3") (pintype "passive"))
      (node (ref "SERVO2") (pin "3") (pinfunction "3_3") (pintype "passive"))
      (node (ref "SERVO3") (pin "3") (pinfunction "3_3") (pintype "passive"))
      (node (ref "SERVO4") (pin "3") (pinfunction "3_3") (pintype "passive"))
      (node (ref "SERVO5") (pin "3") (pinfunction "3_3") (pintype "passive"))
      (node (ref "SERVO6") (pin "3") (pinfunction "3_3") (pintype "passive"))
      (node (ref "TTL_SERIAL") (pin "1") (pinfunction "1_1") (pintype "passive"))
      (node (ref "U$1") (pin "2") (pinfunction "GND_2") (pintype "bidirectional"))
      (node (ref "U2") (pin "8") (pinfunction "E_8") (pintype "power_in"))
      (node (ref "U3") (pin "8") (pinfunction "E_8") (pintype "power_in"))
      (node (ref "X1") (pin "7") (pinfunction "7_7") (pintype "passive"))
      (node (ref "X2") (pin "7") (pinfunction "7_7") (pintype "passive"))
      (node (ref "X3") (pin "7") (pinfunction "7_7") (pintype "passive"))
      (node (ref "X4") (pin "7") (pinfunction "7_7") (pintype "passive"))
      (node (ref "X5") (pin "7") (pinfunction "7_7") (pintype "passive"))
      (node (ref "X6") (pin "7") (pinfunction "7_7") (pintype "passive"))
      (node (ref "X7") (pin "7") (pinfunction "7_7") (pintype "passive"))
      (node (ref "X8") (pin "7") (pinfunction "7_7") (pintype "passive"))
    )
    (net (code "59") (name "Net-(IC1-AREF)") (class "Default")
      (node (ref "C8") (pin "1") (pinfunction "1_1") (pintype "passive"))
      (node (ref "IC1") (pin "29") (pinfunction "AREF_29") (pintype "power_in"))
    )
    (net (code "60") (name "Net-(IC1-XTAL1)") (class "Default")
      (node (ref "IC1") (pin "8") (pinfunction "XTAL1_8") (pintype "input"))
      (node (ref "U$1") (pin "3") (pinfunction "OUT_3") (pintype "bidirectional"))
    )
    (net (code "61") (name "Net-(IC1-XTAL2)") (class "Default")
      (node (ref "IC1") (pin "7") (pinfunction "XTAL2_7") (pintype "output"))
      (node (ref "U$1") (pin "1") (pinfunction "IN_1") (pintype "bidirectional"))
    )
    (net (code "62") (name "Net-(ON-PadC)") (class "Default")
      (node (ref "ON") (pin "C") (pinfunction "C_C") (pintype "passive"))
      (node (ref "R5") (pin "1") (pinfunction "1_1") (pintype "passive"))
    )
    (net (code "63") (name "Net-(R1-Pad1)") (class "Default")
      (node (ref "R1") (pin "1") (pinfunction "1_1") (pintype "passive"))
      (node (ref "X8") (pin "3") (pinfunction "3_3") (pintype "passive"))
    )
    (net (code "64") (name "Net-(R1-Pad2)") (class "Default")
      (node (ref "R1") (pin "2") (pinfunction "2_2") (pintype "passive"))
      (node (ref "X7") (pin "3") (pinfunction "3_3") (pintype "passive"))
    )
    (net (code "65") (name "Net-(R1-Pad3)") (class "Default")
      (node (ref "R1") (pin "3") (pinfunction "3_3") (pintype "passive"))
      (node (ref "X6") (pin "3") (pinfunction "3_3") (pintype "passive"))
    )
    (net (code "66") (name "Net-(R1-Pad4)") (class "Default")
      (node (ref "R1") (pin "4") (pinfunction "4_4") (pintype "passive"))
      (node (ref "X5") (pin "3") (pinfunction "3_3") (pintype "passive"))
    )
    (net (code "67") (name "Net-(R1-Pad5)") (class "Default")
      (node (ref "R1") (pin "5") (pinfunction "5_5") (pintype "passive"))
      (node (ref "X4") (pin "3") (pinfunction "3_3") (pintype "passive"))
    )
    (net (code "68") (name "Net-(R1-Pad6)") (class "Default")
      (node (ref "R1") (pin "6") (pinfunction "6_6") (pintype "passive"))
      (node (ref "X1") (pin "3") (pinfunction "3_3") (pintype "passive"))
    )
    (net (code "69") (name "Net-(R1-Pad7)") (class "Default")
      (node (ref "R1") (pin "7") (pinfunction "7_7") (pintype "passive"))
      (node (ref "X2") (pin "3") (pinfunction "3_3") (pintype "passive"))
    )
    (net (code "70") (name "Net-(R1-Pad8)") (class "Default")
      (node (ref "R1") (pin "8") (pinfunction "8_8") (pintype "passive"))
      (node (ref "X3") (pin "3") (pinfunction "3_3") (pintype "passive"))
    )
    (net (code "71") (name "unconnected-(IC9A-W-Pad6)") (class "Default")
      (node (ref "IC9") (pin "6") (pinfunction "W_6") (pintype "output"))
    )
    (net (code "72") (name "unconnected-(JTAG-Pad7)") (class "Default")
      (node (ref "JTAG") (pin "7") (pinfunction "7_7") (pintype "passive"))
    )
    (net (code "73") (name "unconnected-(JTAG-Pad8)") (class "Default")
      (node (ref "JTAG") (pin "8") (pinfunction "8_8") (pintype "passive"))
    )
    (net (code "74") (name "unconnected-(TTL_SERIAL-Pad2)") (class "Default")
      (node (ref "TTL_SERIAL") (pin "2") (pinfunction "2_2") (pintype "passive"))
    )
    (net (code "75") (name "unconnected-(TTL_SERIAL-Pad3)") (class "Default")
      (node (ref "TTL_SERIAL") (pin "3") (pinfunction "3_3") (pintype "passive"))
    )
    (net (code "76") (name "unconnected-(TTL_SERIAL-Pad6)") (class "Default")
      (node (ref "TTL_SERIAL") (pin "6") (pinfunction "6_6") (pintype "passive"))
    )
    (net (code "77") (name "unconnected-(X1-Pad2)") (class "Default")
      (node (ref "X1") (pin "2") (pinfunction "2_2") (pintype "passive"))
    )
    (net (code "78") (name "unconnected-(X1-Pad5)") (class "Default")
      (node (ref "X1") (pin "5") (pinfunction "5_5") (pintype "passive"))
    )
    (net (code "79") (name "unconnected-(X2-Pad2)") (class "Default")
      (node (ref "X2") (pin "2") (pinfunction "2_2") (pintype "passive"))
    )
    (net (code "80") (name "unconnected-(X2-Pad5)") (class "Default")
      (node (ref "X2") (pin "5") (pinfunction "5_5") (pintype "passive"))
    )
    (net (code "81") (name "unconnected-(X3-Pad2)") (class "Default")
      (node (ref "X3") (pin "2") (pinfunction "2_2") (pintype "passive"))
    )
    (net (code "82") (name "unconnected-(X3-Pad5)") (class "Default")
      (node (ref "X3") (pin "5") (pinfunction "5_5") (pintype "passive"))
    )
    (net (code "83") (name "unconnected-(X4-Pad2)") (class "Default")
      (node (ref "X4") (pin "2") (pinfunction "2_2") (pintype "passive"))
    )
    (net (code "84") (name "unconnected-(X4-Pad5)") (class "Default")
      (node (ref "X4") (pin "5") (pinfunction "5_5") (pintype "passive"))
    )
    (net (code "85") (name "unconnected-(X5-Pad2)") (class "Default")
      (node (ref "X5") (pin "2") (pinfunction "2_2") (pintype "passive"))
    )
    (net (code "86") (name "unconnected-(X5-Pad5)") (class "Default")
      (node (ref "X5") (pin "5") (pinfunction "5_5") (pintype "passive"))
    )
    (net (code "87") (name "unconnected-(X6-Pad2)") (class "Default")
      (node (ref "X6") (pin "2") (pinfunction "2_2") (pintype "passive"))
    )
    (net (code "88") (name "unconnected-(X6-Pad5)") (class "Default")
      (node (ref "X6") (pin "5") (pinfunction "5_5") (pintype "passive"))
    )
    (net (code "89") (name "unconnected-(X7-Pad2)") (class "Default")
      (node (ref "X7") (pin "2") (pinfunction "2_2") (pintype "passive"))
    )
    (net (code "90") (name "unconnected-(X7-Pad5)") (class "Default")
      (node (ref "X7") (pin "5") (pinfunction "5_5") (pintype "passive"))
    )
    (net (code "91") (name "unconnected-(X8-Pad2)") (class "Default")
      (node (ref "X8") (pin "2") (pinfunction "2_2") (pintype "passive"))
    )
    (net (code "92") (name "unconnected-(X8-Pad5)") (class "Default")
      (node (ref "X8") (pin "5") (pinfunction "5_5") (pintype "passive"))
    )
  )
)
